# con-right-bot.net
KiCad netlist of a schematic drawn in Altium Designer
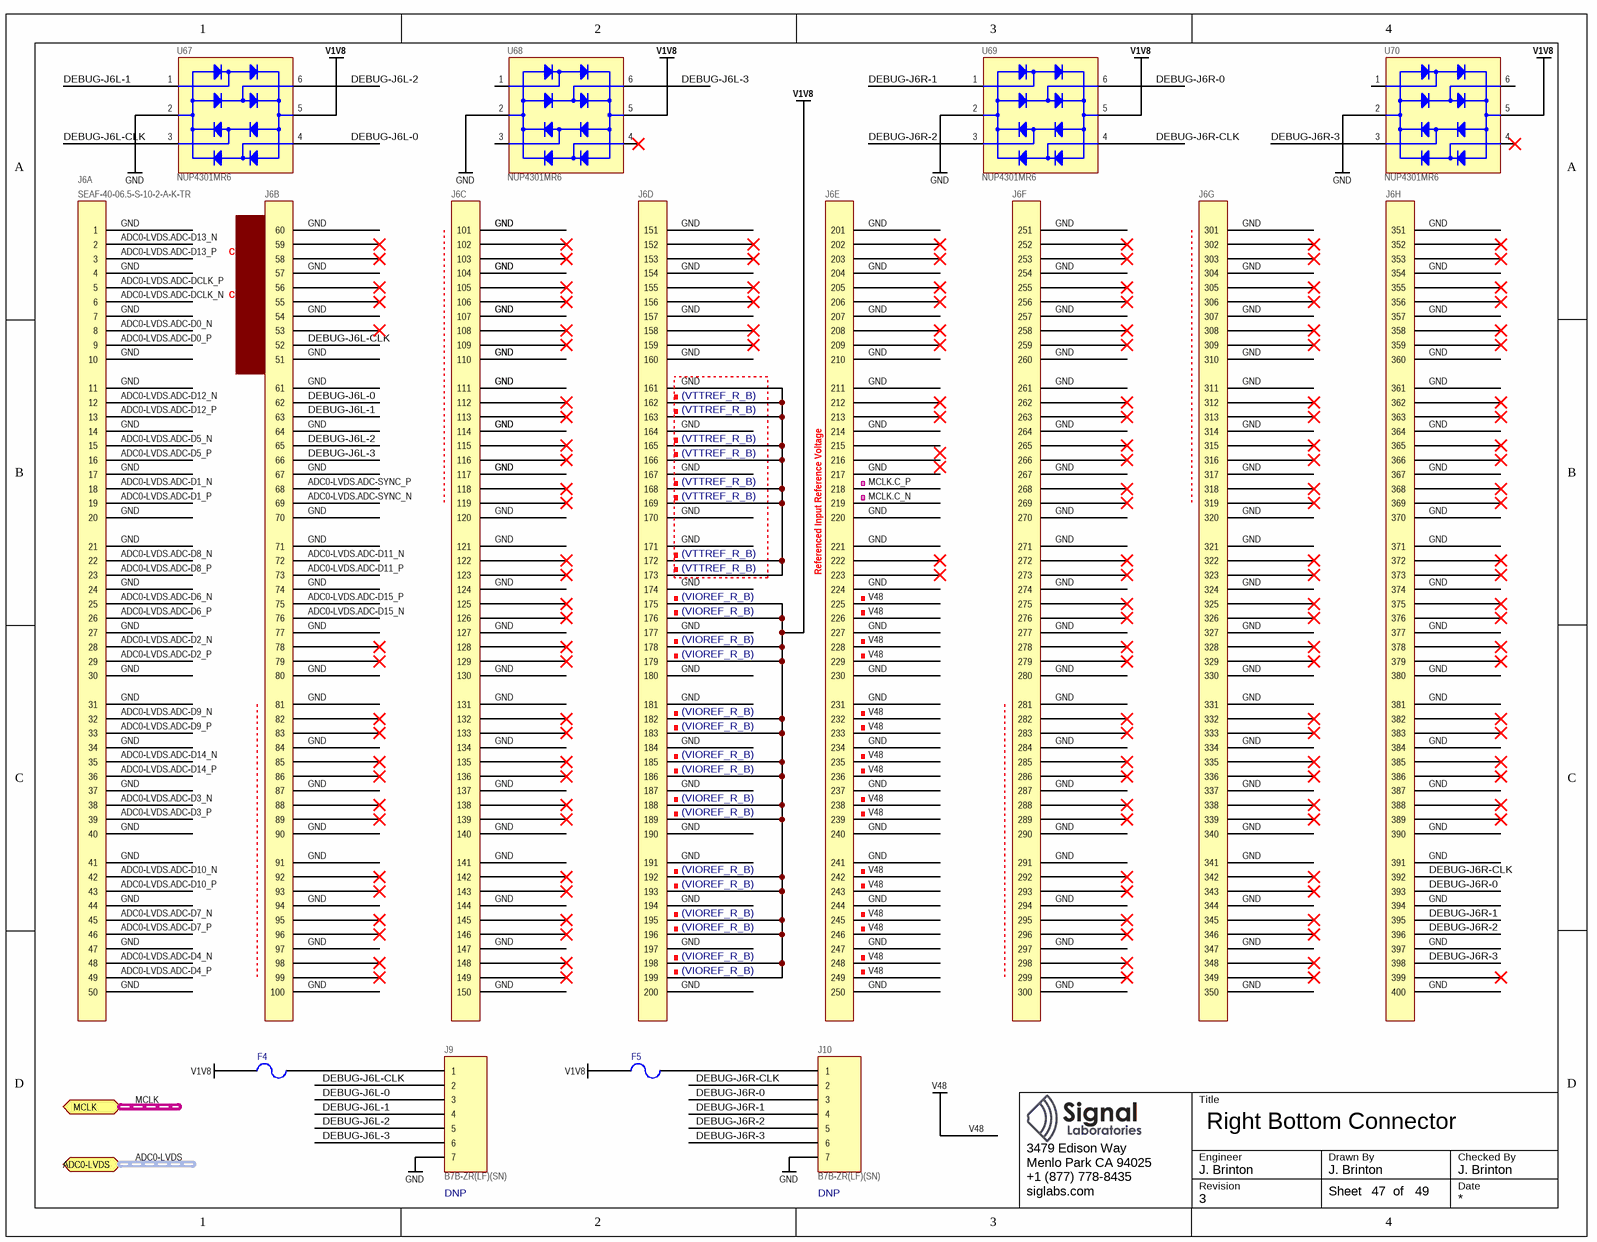
[diagram p0: con-right-bot.SchDoc]

(export (version "E")
  (design (tool "Eeschema 10.0.6"))
  (components
    (comp (ref "F4")
      (value "0ZCJ0020FF2E")
      (footprint "generic:1206")
      (description "PTC Resettable Fuse, 0.2A, 30V, SMD 1206")
      (fields (field (name "MANUFACTURER") "Bell Fuse"))
      (libsource (lib "bel-fuse") (part "0ZCJ0020FF2E"))
    )
    (comp (ref "F5")
      (value "0ZCJ0020FF2E")
      (footprint "generic:1206")
      (description "PTC Resettable Fuse, 0.2A, 30V, SMD 1206")
      (fields (field (name "MANUFACTURER") "Bell Fuse"))
      (libsource (lib "bel-fuse") (part "0ZCJ0020FF2E"))
    )
    (comp (ref "J6")
      (value "SEAF-40-06.5-S-10-2-A-K-TR")
      (footprint "samtec:SEAF-40-06.5-S-10-2-A-K-TR")
      (description "Terminal Array Assembly, Surface Mount, 0.050\" Pitch, 400 Pins")
      (fields (field (name "MANUFACTURER") "Samtec"))
      (libsource (lib "samtec") (part "SEAF-40-06.5-S-10-2-A-K-TR"))
    )
    (comp (ref "J9")
      (value "B7B-ZR(LF)(SN)")
      (footprint "jst:B7B-ZR")
      (description "Through-hole Shrouded Header 7-Position")
      (fields (field (name "MANUFACTURER") "JST") (field (name "DO NOT PLACE") "DNP"))
      (libsource (lib "jst") (part "B7B-ZR(LF)(SN)"))
    )
    (comp (ref "J10")
      (value "B7B-ZR(LF)(SN)")
      (footprint "jst:B7B-ZR")
      (description "Through-hole Shrouded Header 7-Position")
      (fields (field (name "MANUFACTURER") "JST") (field (name "DO NOT PLACE") "DNP"))
      (libsource (lib "jst") (part "B7B-ZR(LF)(SN)"))
    )
    (comp (ref "U67")
      (value "NUP4301MR6")
      (footprint "generic:SOT23-6")
      (description "4-Lane TVS Diode Array")
      (fields (field (name "MANUFACTURER") "On Semiconductor"))
      (libsource (lib "on_semi") (part "NUP4301MR6"))
    )
    (comp (ref "U68")
      (value "NUP4301MR6")
      (footprint "generic:SOT23-6")
      (description "4-Lane TVS Diode Array")
      (fields (field (name "MANUFACTURER") "On Semiconductor"))
      (libsource (lib "on_semi") (part "NUP4301MR6"))
    )
    (comp (ref "U69")
      (value "NUP4301MR6")
      (footprint "generic:SOT23-6")
      (description "4-Lane TVS Diode Array")
      (fields (field (name "MANUFACTURER") "On Semiconductor"))
      (libsource (lib "on_semi") (part "NUP4301MR6"))
    )
    (comp (ref "U70")
      (value "NUP4301MR6")
      (footprint "generic:SOT23-6")
      (description "4-Lane TVS Diode Array")
      (fields (field (name "MANUFACTURER") "On Semiconductor"))
      (libsource (lib "on_semi") (part "NUP4301MR6"))
    )
  )
  (nets
    (net (code "3") (name "/ADC0-LVDS.ADC-D0_N") (class "Default")
      (node (ref "J6") (pin "8") (pinfunction "8_8") (pintype "passive"))
    )
    (net (code "4") (name "/ADC0-LVDS.ADC-D0_P") (class "Default")
      (node (ref "J6") (pin "9") (pinfunction "9_9") (pintype "passive"))
    )
    (net (code "5") (name "/ADC0-LVDS.ADC-D1_N") (class "Default")
      (node (ref "J6") (pin "18") (pinfunction "18_18") (pintype "passive"))
    )
    (net (code "6") (name "/ADC0-LVDS.ADC-D1_P") (class "Default")
      (node (ref "J6") (pin "19") (pinfunction "19_19") (pintype "passive"))
    )
    (net (code "7") (name "/ADC0-LVDS.ADC-D2_N") (class "Default")
      (node (ref "J6") (pin "28") (pinfunction "28_28") (pintype "passive"))
    )
    (net (code "8") (name "/ADC0-LVDS.ADC-D2_P") (class "Default")
      (node (ref "J6") (pin "29") (pinfunction "29_29") (pintype "passive"))
    )
    (net (code "9") (name "/ADC0-LVDS.ADC-D3_N") (class "Default")
      (node (ref "J6") (pin "38") (pinfunction "38_38") (pintype "passive"))
    )
    (net (code "10") (name "/ADC0-LVDS.ADC-D3_P") (class "Default")
      (node (ref "J6") (pin "39") (pinfunction "39_39") (pintype "passive"))
    )
    (net (code "11") (name "/ADC0-LVDS.ADC-D4_N") (class "Default")
      (node (ref "J6") (pin "48") (pinfunction "48_48") (pintype "passive"))
    )
    (net (code "12") (name "/ADC0-LVDS.ADC-D4_P") (class "Default")
      (node (ref "J6") (pin "49") (pinfunction "49_49") (pintype "passive"))
    )
    (net (code "13") (name "/ADC0-LVDS.ADC-D5_N") (class "Default")
      (node (ref "J6") (pin "15") (pinfunction "15_15") (pintype "passive"))
    )
    (net (code "14") (name "/ADC0-LVDS.ADC-D5_P") (class "Default")
      (node (ref "J6") (pin "16") (pinfunction "16_16") (pintype "passive"))
    )
    (net (code "15") (name "/ADC0-LVDS.ADC-D6_N") (class "Default")
      (node (ref "J6") (pin "25") (pinfunction "25_25") (pintype "passive"))
    )
    (net (code "16") (name "/ADC0-LVDS.ADC-D6_P") (class "Default")
      (node (ref "J6") (pin "26") (pinfunction "26_26") (pintype "passive"))
    )
    (net (code "17") (name "/ADC0-LVDS.ADC-D7_N") (class "Default")
      (node (ref "J6") (pin "45") (pinfunction "45_45") (pintype "passive"))
    )
    (net (code "18") (name "/ADC0-LVDS.ADC-D7_P") (class "Default")
      (node (ref "J6") (pin "46") (pinfunction "46_46") (pintype "passive"))
    )
    (net (code "19") (name "/ADC0-LVDS.ADC-D8_N") (class "Default")
      (node (ref "J6") (pin "22") (pinfunction "22_22") (pintype "passive"))
    )
    (net (code "20") (name "/ADC0-LVDS.ADC-D8_P") (class "Default")
      (node (ref "J6") (pin "23") (pinfunction "23_23") (pintype "passive"))
    )
    (net (code "21") (name "/ADC0-LVDS.ADC-D9_N") (class "Default")
      (node (ref "J6") (pin "32") (pinfunction "32_32") (pintype "passive"))
    )
    (net (code "22") (name "/ADC0-LVDS.ADC-D9_P") (class "Default")
      (node (ref "J6") (pin "33") (pinfunction "33_33") (pintype "passive"))
    )
    (net (code "23") (name "/ADC0-LVDS.ADC-D10_N") (class "Default")
      (node (ref "J6") (pin "42") (pinfunction "42_42") (pintype "passive"))
    )
    (net (code "24") (name "/ADC0-LVDS.ADC-D10_P") (class "Default")
      (node (ref "J6") (pin "43") (pinfunction "43_43") (pintype "passive"))
    )
    (net (code "25") (name "/ADC0-LVDS.ADC-D11_N") (class "Default")
      (node (ref "J6") (pin "72") (pinfunction "72_72") (pintype "passive"))
    )
    (net (code "26") (name "/ADC0-LVDS.ADC-D11_P") (class "Default")
      (node (ref "J6") (pin "73") (pinfunction "73_73") (pintype "passive"))
    )
    (net (code "27") (name "/ADC0-LVDS.ADC-D12_N") (class "Default")
      (node (ref "J6") (pin "12") (pinfunction "12_12") (pintype "passive"))
    )
    (net (code "28") (name "/ADC0-LVDS.ADC-D12_P") (class "Default")
      (node (ref "J6") (pin "13") (pinfunction "13_13") (pintype "passive"))
    )
    (net (code "29") (name "/ADC0-LVDS.ADC-D13_N") (class "Default")
      (node (ref "J6") (pin "2") (pinfunction "2_2") (pintype "passive"))
    )
    (net (code "30") (name "/ADC0-LVDS.ADC-D13_P") (class "Default")
      (node (ref "J6") (pin "3") (pinfunction "3_3") (pintype "passive"))
    )
    (net (code "31") (name "/ADC0-LVDS.ADC-D14_N") (class "Default")
      (node (ref "J6") (pin "35") (pinfunction "35_35") (pintype "passive"))
    )
    (net (code "32") (name "/ADC0-LVDS.ADC-D14_P") (class "Default")
      (node (ref "J6") (pin "36") (pinfunction "36_36") (pintype "passive"))
    )
    (net (code "33") (name "/ADC0-LVDS.ADC-D15_N") (class "Default")
      (node (ref "J6") (pin "76") (pinfunction "76_76") (pintype "passive"))
    )
    (net (code "34") (name "/ADC0-LVDS.ADC-D15_P") (class "Default")
      (node (ref "J6") (pin "75") (pinfunction "75_75") (pintype "passive"))
    )
    (net (code "35") (name "/ADC0-LVDS.ADC-DCLK_N") (class "Default")
      (node (ref "J6") (pin "6") (pinfunction "6_6") (pintype "passive"))
    )
    (net (code "36") (name "/ADC0-LVDS.ADC-DCLK_P") (class "Default")
      (node (ref "J6") (pin "5") (pinfunction "5_5") (pintype "passive"))
    )
    (net (code "37") (name "/ADC0-LVDS.ADC-SYNC_N") (class "Default")
      (node (ref "J6") (pin "69") (pinfunction "69_69") (pintype "passive"))
    )
    (net (code "38") (name "/ADC0-LVDS.ADC-SYNC_P") (class "Default")
      (node (ref "J6") (pin "68") (pinfunction "68_68") (pintype "passive"))
    )
    (net (code "39") (name "/DEBUG-J6L-0") (class "Default")
      (node (ref "J6") (pin "62") (pinfunction "62_62") (pintype "passive"))
      (node (ref "J9") (pin "3") (pinfunction "3_3") (pintype "passive"))
      (node (ref "U67") (pin "4") (pinfunction "C_4") (pintype "passive"))
    )
    (net (code "40") (name "/DEBUG-J6L-1") (class "Default")
      (node (ref "J6") (pin "63") (pinfunction "63_63") (pintype "passive"))
      (node (ref "J9") (pin "4") (pinfunction "4_4") (pintype "passive"))
      (node (ref "U67") (pin "1") (pinfunction "A_1") (pintype "passive"))
    )
    (net (code "41") (name "/DEBUG-J6L-2") (class "Default")
      (node (ref "J6") (pin "65") (pinfunction "65_65") (pintype "passive"))
      (node (ref "J9") (pin "5") (pinfunction "5_5") (pintype "passive"))
      (node (ref "U67") (pin "6") (pinfunction "D_6") (pintype "passive"))
    )
    (net (code "42") (name "/DEBUG-J6L-3") (class "Default")
      (node (ref "J6") (pin "66") (pinfunction "66_66") (pintype "passive"))
      (node (ref "J9") (pin "6") (pinfunction "6_6") (pintype "passive"))
      (node (ref "U68") (pin "6") (pinfunction "D_6") (pintype "passive"))
    )
    (net (code "43") (name "/DEBUG-J6L-CLK") (class "Default")
      (node (ref "J6") (pin "52") (pinfunction "52_52") (pintype "passive"))
      (node (ref "J9") (pin "2") (pinfunction "2_2") (pintype "passive"))
      (node (ref "U67") (pin "3") (pinfunction "B_3") (pintype "passive"))
    )
    (net (code "44") (name "/DEBUG-J6R-0") (class "Default")
      (node (ref "J10") (pin "3") (pinfunction "3_3") (pintype "passive"))
      (node (ref "J6") (pin "393") (pinfunction "393_393") (pintype "passive"))
      (node (ref "U69") (pin "6") (pinfunction "D_6") (pintype "passive"))
    )
    (net (code "45") (name "/DEBUG-J6R-1") (class "Default")
      (node (ref "J10") (pin "4") (pinfunction "4_4") (pintype "passive"))
      (node (ref "J6") (pin "395") (pinfunction "395_395") (pintype "passive"))
      (node (ref "U69") (pin "1") (pinfunction "A_1") (pintype "passive"))
    )
    (net (code "46") (name "/DEBUG-J6R-2") (class "Default")
      (node (ref "J10") (pin "5") (pinfunction "5_5") (pintype "passive"))
      (node (ref "J6") (pin "396") (pinfunction "396_396") (pintype "passive"))
      (node (ref "U69") (pin "3") (pinfunction "B_3") (pintype "passive"))
    )
    (net (code "47") (name "/DEBUG-J6R-3") (class "Default")
      (node (ref "J10") (pin "6") (pinfunction "6_6") (pintype "passive"))
      (node (ref "J6") (pin "398") (pinfunction "398_398") (pintype "passive"))
      (node (ref "U70") (pin "3") (pinfunction "B_3") (pintype "passive"))
    )
    (net (code "48") (name "/DEBUG-J6R-CLK") (class "Default")
      (node (ref "J10") (pin "2") (pinfunction "2_2") (pintype "passive"))
      (node (ref "J6") (pin "392") (pinfunction "392_392") (pintype "passive"))
      (node (ref "U69") (pin "4") (pinfunction "C_4") (pintype "passive"))
    )
    (net (code "49") (name "/MCLK.C_N") (class "Default")
      (node (ref "J6") (pin "219") (pinfunction "219_219") (pintype "passive"))
    )
    (net (code "50") (name "/MCLK.C_P") (class "Default")
      (node (ref "J6") (pin "218") (pinfunction "218_218") (pintype "passive"))
    )
    (net (code "53") (name "GND") (class "Default")
      (node (ref "J10") (pin "7") (pinfunction "7_7") (pintype "passive"))
      (node (ref "J6") (pin "1") (pinfunction "1_1") (pintype "passive"))
      (node (ref "J6") (pin "10") (pinfunction "10_10") (pintype "passive"))
      (node (ref "J6") (pin "100") (pinfunction "100_100") (pintype "passive"))
      (node (ref "J6") (pin "101") (pinfunction "101_101") (pintype "passive"))
      (node (ref "J6") (pin "104") (pinfunction "104_104") (pintype "passive"))
      (node (ref "J6") (pin "107") (pinfunction "107_107") (pintype "passive"))
      (node (ref "J6") (pin "11") (pinfunction "11_11") (pintype "passive"))
      (node (ref "J6") (pin "110") (pinfunction "110_110") (pintype "passive"))
      (node (ref "J6") (pin "111") (pinfunction "111_111") (pintype "passive"))
      (node (ref "J6") (pin "114") (pinfunction "114_114") (pintype "passive"))
      (node (ref "J6") (pin "117") (pinfunction "117_117") (pintype "passive"))
      (node (ref "J6") (pin "120") (pinfunction "120_120") (pintype "passive"))
      (node (ref "J6") (pin "121") (pinfunction "121_121") (pintype "passive"))
      (node (ref "J6") (pin "124") (pinfunction "124_124") (pintype "passive"))
      (node (ref "J6") (pin "127") (pinfunction "127_127") (pintype "passive"))
      (node (ref "J6") (pin "130") (pinfunction "130_130") (pintype "passive"))
      (node (ref "J6") (pin "131") (pinfunction "131_131") (pintype "passive"))
      (node (ref "J6") (pin "134") (pinfunction "134_134") (pintype "passive"))
      (node (ref "J6") (pin "137") (pinfunction "137_137") (pintype "passive"))
      (node (ref "J6") (pin "14") (pinfunction "14_14") (pintype "passive"))
      (node (ref "J6") (pin "140") (pinfunction "140_140") (pintype "passive"))
      (node (ref "J6") (pin "141") (pinfunction "141_141") (pintype "passive"))
      (node (ref "J6") (pin "144") (pinfunction "144_144") (pintype "passive"))
      (node (ref "J6") (pin "147") (pinfunction "147_147") (pintype "passive"))
      (node (ref "J6") (pin "150") (pinfunction "150_150") (pintype "passive"))
      (node (ref "J6") (pin "151") (pinfunction "151_151") (pintype "passive"))
      (node (ref "J6") (pin "154") (pinfunction "154_154") (pintype "passive"))
      (node (ref "J6") (pin "157") (pinfunction "157_157") (pintype "passive"))
      (node (ref "J6") (pin "160") (pinfunction "160_160") (pintype "passive"))
      (node (ref "J6") (pin "161") (pinfunction "161_161") (pintype "passive"))
      (node (ref "J6") (pin "162") (pinfunction "162_162") (pintype "passive"))
      (node (ref "J6") (pin "163") (pinfunction "163_163") (pintype "passive"))
      (node (ref "J6") (pin "164") (pinfunction "164_164") (pintype "passive"))
      (node (ref "J6") (pin "165") (pinfunction "165_165") (pintype "passive"))
      (node (ref "J6") (pin "166") (pinfunction "166_166") (pintype "passive"))
      (node (ref "J6") (pin "167") (pinfunction "167_167") (pintype "passive"))
      (node (ref "J6") (pin "168") (pinfunction "168_168") (pintype "passive"))
      (node (ref "J6") (pin "169") (pinfunction "169_169") (pintype "passive"))
      (node (ref "J6") (pin "17") (pinfunction "17_17") (pintype "passive"))
      (node (ref "J6") (pin "170") (pinfunction "170_170") (pintype "passive"))
      (node (ref "J6") (pin "171") (pinfunction "171_171") (pintype "passive"))
      (node (ref "J6") (pin "172") (pinfunction "172_172") (pintype "passive"))
      (node (ref "J6") (pin "173") (pinfunction "173_173") (pintype "passive"))
      (node (ref "J6") (pin "174") (pinfunction "174_174") (pintype "passive"))
      (node (ref "J6") (pin "177") (pinfunction "177_177") (pintype "passive"))
      (node (ref "J6") (pin "180") (pinfunction "180_180") (pintype "passive"))
      (node (ref "J6") (pin "181") (pinfunction "181_181") (pintype "passive"))
      (node (ref "J6") (pin "184") (pinfunction "184_184") (pintype "passive"))
      (node (ref "J6") (pin "187") (pinfunction "187_187") (pintype "passive"))
      (node (ref "J6") (pin "190") (pinfunction "190_190") (pintype "passive"))
      (node (ref "J6") (pin "191") (pinfunction "191_191") (pintype "passive"))
      (node (ref "J6") (pin "194") (pinfunction "194_194") (pintype "passive"))
      (node (ref "J6") (pin "197") (pinfunction "197_197") (pintype "passive"))
      (node (ref "J6") (pin "20") (pinfunction "20_20") (pintype "passive"))
      (node (ref "J6") (pin "200") (pinfunction "200_200") (pintype "passive"))
      (node (ref "J6") (pin "201") (pinfunction "201_201") (pintype "passive"))
      (node (ref "J6") (pin "204") (pinfunction "204_204") (pintype "passive"))
      (node (ref "J6") (pin "207") (pinfunction "207_207") (pintype "passive"))
      (node (ref "J6") (pin "21") (pinfunction "21_21") (pintype "passive"))
      (node (ref "J6") (pin "210") (pinfunction "210_210") (pintype "passive"))
      (node (ref "J6") (pin "211") (pinfunction "211_211") (pintype "passive"))
      (node (ref "J6") (pin "214") (pinfunction "214_214") (pintype "passive"))
      (node (ref "J6") (pin "217") (pinfunction "217_217") (pintype "passive"))
      (node (ref "J6") (pin "220") (pinfunction "220_220") (pintype "passive"))
      (node (ref "J6") (pin "221") (pinfunction "221_221") (pintype "passive"))
      (node (ref "J6") (pin "224") (pinfunction "224_224") (pintype "passive"))
      (node (ref "J6") (pin "227") (pinfunction "227_227") (pintype "passive"))
      (node (ref "J6") (pin "230") (pinfunction "230_230") (pintype "passive"))
      (node (ref "J6") (pin "231") (pinfunction "231_231") (pintype "passive"))
      (node (ref "J6") (pin "234") (pinfunction "234_234") (pintype "passive"))
      (node (ref "J6") (pin "237") (pinfunction "237_237") (pintype "passive"))
      (node (ref "J6") (pin "24") (pinfunction "24_24") (pintype "passive"))
      (node (ref "J6") (pin "240") (pinfunction "240_240") (pintype "passive"))
      (node (ref "J6") (pin "241") (pinfunction "241_241") (pintype "passive"))
      (node (ref "J6") (pin "244") (pinfunction "244_244") (pintype "passive"))
      (node (ref "J6") (pin "247") (pinfunction "247_247") (pintype "passive"))
      (node (ref "J6") (pin "250") (pinfunction "250_250") (pintype "passive"))
      (node (ref "J6") (pin "251") (pinfunction "251_251") (pintype "passive"))
      (node (ref "J6") (pin "254") (pinfunction "254_254") (pintype "passive"))
      (node (ref "J6") (pin "257") (pinfunction "257_257") (pintype "passive"))
      (node (ref "J6") (pin "260") (pinfunction "260_260") (pintype "passive"))
      (node (ref "J6") (pin "261") (pinfunction "261_261") (pintype "passive"))
      (node (ref "J6") (pin "264") (pinfunction "264_264") (pintype "passive"))
      (node (ref "J6") (pin "267") (pinfunction "267_267") (pintype "passive"))
      (node (ref "J6") (pin "27") (pinfunction "27_27") (pintype "passive"))
      (node (ref "J6") (pin "270") (pinfunction "270_270") (pintype "passive"))
      (node (ref "J6") (pin "271") (pinfunction "271_271") (pintype "passive"))
      (node (ref "J6") (pin "274") (pinfunction "274_274") (pintype "passive"))
      (node (ref "J6") (pin "277") (pinfunction "277_277") (pintype "passive"))
      (node (ref "J6") (pin "280") (pinfunction "280_280") (pintype "passive"))
      (node (ref "J6") (pin "281") (pinfunction "281_281") (pintype "passive"))
      (node (ref "J6") (pin "284") (pinfunction "284_284") (pintype "passive"))
      (node (ref "J6") (pin "287") (pinfunction "287_287") (pintype "passive"))
      (node (ref "J6") (pin "290") (pinfunction "290_290") (pintype "passive"))
      (node (ref "J6") (pin "291") (pinfunction "291_291") (pintype "passive"))
      (node (ref "J6") (pin "294") (pinfunction "294_294") (pintype "passive"))
      (node (ref "J6") (pin "297") (pinfunction "297_297") (pintype "passive"))
      (node (ref "J6") (pin "30") (pinfunction "30_30") (pintype "passive"))
      (node (ref "J6") (pin "300") (pinfunction "300_300") (pintype "passive"))
      (node (ref "J6") (pin "301") (pinfunction "301_301") (pintype "passive"))
      (node (ref "J6") (pin "304") (pinfunction "304_304") (pintype "passive"))
      (node (ref "J6") (pin "307") (pinfunction "307_307") (pintype "passive"))
      (node (ref "J6") (pin "31") (pinfunction "31_31") (pintype "passive"))
      (node (ref "J6") (pin "310") (pinfunction "310_310") (pintype "passive"))
      (node (ref "J6") (pin "311") (pinfunction "311_311") (pintype "passive"))
      (node (ref "J6") (pin "314") (pinfunction "314_314") (pintype "passive"))
      (node (ref "J6") (pin "317") (pinfunction "317_317") (pintype "passive"))
      (node (ref "J6") (pin "320") (pinfunction "320_320") (pintype "passive"))
      (node (ref "J6") (pin "321") (pinfunction "321_321") (pintype "passive"))
      (node (ref "J6") (pin "324") (pinfunction "324_324") (pintype "passive"))
      (node (ref "J6") (pin "327") (pinfunction "327_327") (pintype "passive"))
      (node (ref "J6") (pin "330") (pinfunction "330_330") (pintype "passive"))
      (node (ref "J6") (pin "331") (pinfunction "331_331") (pintype "passive"))
      (node (ref "J6") (pin "334") (pinfunction "334_334") (pintype "passive"))
      (node (ref "J6") (pin "337") (pinfunction "337_337") (pintype "passive"))
      (node (ref "J6") (pin "34") (pinfunction "34_34") (pintype "passive"))
      (node (ref "J6") (pin "340") (pinfunction "340_340") (pintype "passive"))
      (node (ref "J6") (pin "341") (pinfunction "341_341") (pintype "passive"))
      (node (ref "J6") (pin "344") (pinfunction "344_344") (pintype "passive"))
      (node (ref "J6") (pin "347") (pinfunction "347_347") (pintype "passive"))
      (node (ref "J6") (pin "350") (pinfunction "350_350") (pintype "passive"))
      (node (ref "J6") (pin "351") (pinfunction "351_351") (pintype "passive"))
      (node (ref "J6") (pin "354") (pinfunction "354_354") (pintype "passive"))
      (node (ref "J6") (pin "357") (pinfunction "357_357") (pintype "passive"))
      (node (ref "J6") (pin "360") (pinfunction "360_360") (pintype "passive"))
      (node (ref "J6") (pin "361") (pinfunction "361_361") (pintype "passive"))
      (node (ref "J6") (pin "364") (pinfunction "364_364") (pintype "passive"))
      (node (ref "J6") (pin "367") (pinfunction "367_367") (pintype "passive"))
      (node (ref "J6") (pin "37") (pinfunction "37_37") (pintype "passive"))
      (node (ref "J6") (pin "370") (pinfunction "370_370") (pintype "passive"))
      (node (ref "J6") (pin "371") (pinfunction "371_371") (pintype "passive"))
      (node (ref "J6") (pin "374") (pinfunction "374_374") (pintype "passive"))
      (node (ref "J6") (pin "377") (pinfunction "377_377") (pintype "passive"))
      (node (ref "J6") (pin "380") (pinfunction "380_380") (pintype "passive"))
      (node (ref "J6") (pin "381") (pinfunction "381_381") (pintype "passive"))
      (node (ref "J6") (pin "384") (pinfunction "384_384") (pintype "passive"))
      (node (ref "J6") (pin "387") (pinfunction "387_387") (pintype "passive"))
      (node (ref "J6") (pin "390") (pinfunction "390_390") (pintype "passive"))
      (node (ref "J6") (pin "391") (pinfunction "391_391") (pintype "passive"))
      (node (ref "J6") (pin "394") (pinfunction "394_394") (pintype "passive"))
      (node (ref "J6") (pin "397") (pinfunction "397_397") (pintype "passive"))
      (node (ref "J6") (pin "4") (pinfunction "4_4") (pintype "passive"))
      (node (ref "J6") (pin "40") (pinfunction "40_40") (pintype "passive"))
      (node (ref "J6") (pin "400") (pinfunction "400_400") (pintype "passive"))
      (node (ref "J6") (pin "41") (pinfunction "41_41") (pintype "passive"))
      (node (ref "J6") (pin "44") (pinfunction "44_44") (pintype "passive"))
      (node (ref "J6") (pin "47") (pinfunction "47_47") (pintype "passive"))
      (node (ref "J6") (pin "50") (pinfunction "50_50") (pintype "passive"))
      (node (ref "J6") (pin "51") (pinfunction "51_51") (pintype "passive"))
      (node (ref "J6") (pin "54") (pinfunction "54_54") (pintype "passive"))
      (node (ref "J6") (pin "57") (pinfunction "57_57") (pintype "passive"))
      (node (ref "J6") (pin "60") (pinfunction "60_60") (pintype "passive"))
      (node (ref "J6") (pin "61") (pinfunction "61_61") (pintype "passive"))
      (node (ref "J6") (pin "64") (pinfunction "64_64") (pintype "passive"))
      (node (ref "J6") (pin "67") (pinfunction "67_67") (pintype "passive"))
      (node (ref "J6") (pin "7") (pinfunction "7_7") (pintype "passive"))
      (node (ref "J6") (pin "70") (pinfunction "70_70") (pintype "passive"))
      (node (ref "J6") (pin "71") (pinfunction "71_71") (pintype "passive"))
      (node (ref "J6") (pin "74") (pinfunction "74_74") (pintype "passive"))
      (node (ref "J6") (pin "77") (pinfunction "77_77") (pintype "passive"))
      (node (ref "J6") (pin "80") (pinfunction "80_80") (pintype "passive"))
      (node (ref "J6") (pin "81") (pinfunction "81_81") (pintype "passive"))
      (node (ref "J6") (pin "84") (pinfunction "84_84") (pintype "passive"))
      (node (ref "J6") (pin "87") (pinfunction "87_87") (pintype "passive"))
      (node (ref "J6") (pin "90") (pinfunction "90_90") (pintype "passive"))
      (node (ref "J6") (pin "91") (pinfunction "91_91") (pintype "passive"))
      (node (ref "J6") (pin "94") (pinfunction "94_94") (pintype "passive"))
      (node (ref "J6") (pin "97") (pinfunction "97_97") (pintype "passive"))
      (node (ref "J9") (pin "7") (pinfunction "7_7") (pintype "passive"))
      (node (ref "U67") (pin "2") (pinfunction "VN_2") (pintype "passive"))
      (node (ref "U68") (pin "2") (pinfunction "VN_2") (pintype "passive"))
      (node (ref "U69") (pin "2") (pinfunction "VN_2") (pintype "passive"))
      (node (ref "U70") (pin "2") (pinfunction "VN_2") (pintype "passive"))
    )
    (net (code "54") (name "Net-(F4-Pad1)") (class "Default")
      (node (ref "F4") (pin "1") (pinfunction "1_1") (pintype "passive"))
      (node (ref "J9") (pin "1") (pinfunction "1_1") (pintype "passive"))
    )
    (net (code "55") (name "Net-(F5-Pad1)") (class "Default")
      (node (ref "F5") (pin "1") (pinfunction "1_1") (pintype "passive"))
      (node (ref "J10") (pin "1") (pinfunction "1_1") (pintype "passive"))
    )
    (net (code "56") (name "V1V8") (class "Default")
      (node (ref "F4") (pin "2") (pinfunction "2_2") (pintype "passive"))
      (node (ref "F5") (pin "2") (pinfunction "2_2") (pintype "passive"))
      (node (ref "J6") (pin "175") (pinfunction "175_175") (pintype "passive"))
      (node (ref "J6") (pin "176") (pinfunction "176_176") (pintype "passive"))
      (node (ref "J6") (pin "178") (pinfunction "178_178") (pintype "passive"))
      (node (ref "J6") (pin "179") (pinfunction "179_179") (pintype "passive"))
      (node (ref "J6") (pin "182") (pinfunction "182_182") (pintype "passive"))
      (node (ref "J6") (pin "183") (pinfunction "183_183") (pintype "passive"))
      (node (ref "J6") (pin "185") (pinfunction "185_185") (pintype "passive"))
      (node (ref "J6") (pin "186") (pinfunction "186_186") (pintype "passive"))
      (node (ref "J6") (pin "188") (pinfunction "188_188") (pintype "passive"))
      (node (ref "J6") (pin "189") (pinfunction "189_189") (pintype "passive"))
      (node (ref "J6") (pin "192") (pinfunction "192_192") (pintype "passive"))
      (node (ref "J6") (pin "193") (pinfunction "193_193") (pintype "passive"))
      (node (ref "J6") (pin "195") (pinfunction "195_195") (pintype "passive"))
      (node (ref "J6") (pin "196") (pinfunction "196_196") (pintype "passive"))
      (node (ref "J6") (pin "198") (pinfunction "198_198") (pintype "passive"))
      (node (ref "J6") (pin "199") (pinfunction "199_199") (pintype "passive"))
      (node (ref "U67") (pin "5") (pinfunction "VP_5") (pintype "passive"))
      (node (ref "U68") (pin "5") (pinfunction "VP_5") (pintype "passive"))
      (node (ref "U69") (pin "5") (pinfunction "VP_5") (pintype "passive"))
      (node (ref "U70") (pin "5") (pinfunction "VP_5") (pintype "passive"))
    )
    (net (code "57") (name "V48") (class "Default")
      (node (ref "J6") (pin "225") (pinfunction "225_225") (pintype "passive"))
      (node (ref "J6") (pin "226") (pinfunction "226_226") (pintype "passive"))
      (node (ref "J6") (pin "228") (pinfunction "228_228") (pintype "passive"))
      (node (ref "J6") (pin "229") (pinfunction "229_229") (pintype "passive"))
      (node (ref "J6") (pin "232") (pinfunction "232_232") (pintype "passive"))
      (node (ref "J6") (pin "233") (pinfunction "233_233") (pintype "passive"))
      (node (ref "J6") (pin "235") (pinfunction "235_235") (pintype "passive"))
      (node (ref "J6") (pin "236") (pinfunction "236_236") (pintype "passive"))
      (node (ref "J6") (pin "238") (pinfunction "238_238") (pintype "passive"))
      (node (ref "J6") (pin "239") (pinfunction "239_239") (pintype "passive"))
      (node (ref "J6") (pin "242") (pinfunction "242_242") (pintype "passive"))
      (node (ref "J6") (pin "243") (pinfunction "243_243") (pintype "passive"))
      (node (ref "J6") (pin "245") (pinfunction "245_245") (pintype "passive"))
      (node (ref "J6") (pin "246") (pinfunction "246_246") (pintype "passive"))
      (node (ref "J6") (pin "248") (pinfunction "248_248") (pintype "passive"))
      (node (ref "J6") (pin "249") (pinfunction "249_249") (pintype "passive"))
    )
    (net (code "58") (name "unconnected-(J6-Pad53)") (class "Default")
      (node (ref "J6") (pin "53") (pinfunction "53_53") (pintype "passive+no_connect"))
    )
    (net (code "59") (name "unconnected-(J6-Pad55)") (class "Default")
      (node (ref "J6") (pin "55") (pinfunction "55_55") (pintype "passive+no_connect"))
    )
    (net (code "60") (name "unconnected-(J6-Pad56)") (class "Default")
      (node (ref "J6") (pin "56") (pinfunction "56_56") (pintype "passive+no_connect"))
    )
    (net (code "61") (name "unconnected-(J6-Pad58)") (class "Default")
      (node (ref "J6") (pin "58") (pinfunction "58_58") (pintype "passive+no_connect"))
    )
    (net (code "62") (name "unconnected-(J6-Pad59)") (class "Default")
      (node (ref "J6") (pin "59") (pinfunction "59_59") (pintype "passive+no_connect"))
    )
    (net (code "63") (name "unconnected-(J6-Pad78)") (class "Default")
      (node (ref "J6") (pin "78") (pinfunction "78_78") (pintype "passive+no_connect"))
    )
    (net (code "64") (name "unconnected-(J6-Pad79)") (class "Default")
      (node (ref "J6") (pin "79") (pinfunction "79_79") (pintype "passive+no_connect"))
    )
    (net (code "65") (name "unconnected-(J6-Pad82)") (class "Default")
      (node (ref "J6") (pin "82") (pinfunction "82_82") (pintype "passive+no_connect"))
    )
    (net (code "66") (name "unconnected-(J6-Pad83)") (class "Default")
      (node (ref "J6") (pin "83") (pinfunction "83_83") (pintype "passive+no_connect"))
    )
    (net (code "67") (name "unconnected-(J6-Pad85)") (class "Default")
      (node (ref "J6") (pin "85") (pinfunction "85_85") (pintype "passive+no_connect"))
    )
    (net (code "68") (name "unconnected-(J6-Pad86)") (class "Default")
      (node (ref "J6") (pin "86") (pinfunction "86_86") (pintype "passive+no_connect"))
    )
    (net (code "69") (name "unconnected-(J6-Pad88)") (class "Default")
      (node (ref "J6") (pin "88") (pinfunction "88_88") (pintype "passive+no_connect"))
    )
    (net (code "70") (name "unconnected-(J6-Pad89)") (class "Default")
      (node (ref "J6") (pin "89") (pinfunction "89_89") (pintype "passive+no_connect"))
    )
    (net (code "71") (name "unconnected-(J6-Pad92)") (class "Default")
      (node (ref "J6") (pin "92") (pinfunction "92_92") (pintype "passive+no_connect"))
    )
    (net (code "72") (name "unconnected-(J6-Pad93)") (class "Default")
      (node (ref "J6") (pin "93") (pinfunction "93_93") (pintype "passive+no_connect"))
    )
    (net (code "73") (name "unconnected-(J6-Pad95)") (class "Default")
      (node (ref "J6") (pin "95") (pinfunction "95_95") (pintype "passive+no_connect"))
    )
    (net (code "74") (name "unconnected-(J6-Pad96)") (class "Default")
      (node (ref "J6") (pin "96") (pinfunction "96_96") (pintype "passive+no_connect"))
    )
    (net (code "75") (name "unconnected-(J6-Pad98)") (class "Default")
      (node (ref "J6") (pin "98") (pinfunction "98_98") (pintype "passive+no_connect"))
    )
    (net (code "76") (name "unconnected-(J6-Pad99)") (class "Default")
      (node (ref "J6") (pin "99") (pinfunction "99_99") (pintype "passive+no_connect"))
    )
    (net (code "77") (name "unconnected-(J6-Pad102)") (class "Default")
      (node (ref "J6") (pin "102") (pinfunction "102_102") (pintype "passive+no_connect"))
    )
    (net (code "78") (name "unconnected-(J6-Pad103)") (class "Default")
      (node (ref "J6") (pin "103") (pinfunction "103_103") (pintype "passive+no_connect"))
    )
    (net (code "79") (name "unconnected-(J6-Pad105)") (class "Default")
      (node (ref "J6") (pin "105") (pinfunction "105_105") (pintype "passive+no_connect"))
    )
    (net (code "80") (name "unconnected-(J6-Pad106)") (class "Default")
      (node (ref "J6") (pin "106") (pinfunction "106_106") (pintype "passive+no_connect"))
    )
    (net (code "81") (name "unconnected-(J6-Pad108)") (class "Default")
      (node (ref "J6") (pin "108") (pinfunction "108_108") (pintype "passive+no_connect"))
    )
    (net (code "82") (name "unconnected-(J6-Pad109)") (class "Default")
      (node (ref "J6") (pin "109") (pinfunction "109_109") (pintype "passive+no_connect"))
    )
    (net (code "83") (name "unconnected-(J6-Pad112)") (class "Default")
      (node (ref "J6") (pin "112") (pinfunction "112_112") (pintype "passive+no_connect"))
    )
    (net (code "84") (name "unconnected-(J6-Pad113)") (class "Default")
      (node (ref "J6") (pin "113") (pinfunction "113_113") (pintype "passive+no_connect"))
    )
    (net (code "85") (name "unconnected-(J6-Pad115)") (class "Default")
      (node (ref "J6") (pin "115") (pinfunction "115_115") (pintype "passive+no_connect"))
    )
    (net (code "86") (name "unconnected-(J6-Pad116)") (class "Default")
      (node (ref "J6") (pin "116") (pinfunction "116_116") (pintype "passive+no_connect"))
    )
    (net (code "87") (name "unconnected-(J6-Pad118)") (class "Default")
      (node (ref "J6") (pin "118") (pinfunction "118_118") (pintype "passive+no_connect"))
    )
    (net (code "88") (name "unconnected-(J6-Pad119)") (class "Default")
      (node (ref "J6") (pin "119") (pinfunction "119_119") (pintype "passive+no_connect"))
    )
    (net (code "89") (name "unconnected-(J6-Pad122)") (class "Default")
      (node (ref "J6") (pin "122") (pinfunction "122_122") (pintype "passive+no_connect"))
    )
    (net (code "90") (name "unconnected-(J6-Pad123)") (class "Default")
      (node (ref "J6") (pin "123") (pinfunction "123_123") (pintype "passive+no_connect"))
    )
    (net (code "91") (name "unconnected-(J6-Pad125)") (class "Default")
      (node (ref "J6") (pin "125") (pinfunction "125_125") (pintype "passive+no_connect"))
    )
    (net (code "92") (name "unconnected-(J6-Pad126)") (class "Default")
      (node (ref "J6") (pin "126") (pinfunction "126_126") (pintype "passive+no_connect"))
    )
    (net (code "93") (name "unconnected-(J6-Pad128)") (class "Default")
      (node (ref "J6") (pin "128") (pinfunction "128_128") (pintype "passive+no_connect"))
    )
    (net (code "94") (name "unconnected-(J6-Pad129)") (class "Default")
      (node (ref "J6") (pin "129") (pinfunction "129_129") (pintype "passive+no_connect"))
    )
    (net (code "95") (name "unconnected-(J6-Pad132)") (class "Default")
      (node (ref "J6") (pin "132") (pinfunction "132_132") (pintype "passive+no_connect"))
    )
    (net (code "96") (name "unconnected-(J6-Pad133)") (class "Default")
      (node (ref "J6") (pin "133") (pinfunction "133_133") (pintype "passive+no_connect"))
    )
    (net (code "97") (name "unconnected-(J6-Pad135)") (class "Default")
      (node (ref "J6") (pin "135") (pinfunction "135_135") (pintype "passive+no_connect"))
    )
    (net (code "98") (name "unconnected-(J6-Pad136)") (class "Default")
      (node (ref "J6") (pin "136") (pinfunction "136_136") (pintype "passive+no_connect"))
    )
    (net (code "99") (name "unconnected-(J6-Pad138)") (class "Default")
      (node (ref "J6") (pin "138") (pinfunction "138_138") (pintype "passive+no_connect"))
    )
    (net (code "100") (name "unconnected-(J6-Pad139)") (class "Default")
      (node (ref "J6") (pin "139") (pinfunction "139_139") (pintype "passive+no_connect"))
    )
    (net (code "101") (name "unconnected-(J6-Pad142)") (class "Default")
      (node (ref "J6") (pin "142") (pinfunction "142_142") (pintype "passive+no_connect"))
    )
    (net (code "102") (name "unconnected-(J6-Pad143)") (class "Default")
      (node (ref "J6") (pin "143") (pinfunction "143_143") (pintype "passive+no_connect"))
    )
    (net (code "103") (name "unconnected-(J6-Pad145)") (class "Default")
      (node (ref "J6") (pin "145") (pinfunction "145_145") (pintype "passive+no_connect"))
    )
    (net (code "104") (name "unconnected-(J6-Pad146)") (class "Default")
      (node (ref "J6") (pin "146") (pinfunction "146_146") (pintype "passive+no_connect"))
    )
    (net (code "105") (name "unconnected-(J6-Pad148)") (class "Default")
      (node (ref "J6") (pin "148") (pinfunction "148_148") (pintype "passive+no_connect"))
    )
    (net (code "106") (name "unconnected-(J6-Pad149)") (class "Default")
      (node (ref "J6") (pin "149") (pinfunction "149_149") (pintype "passive+no_connect"))
    )
    (net (code "107") (name "unconnected-(J6-Pad152)") (class "Default")
      (node (ref "J6") (pin "152") (pinfunction "152_152") (pintype "passive+no_connect"))
    )
    (net (code "108") (name "unconnected-(J6-Pad153)") (class "Default")
      (node (ref "J6") (pin "153") (pinfunction "153_153") (pintype "passive+no_connect"))
    )
    (net (code "109") (name "unconnected-(J6-Pad155)") (class "Default")
      (node (ref "J6") (pin "155") (pinfunction "155_155") (pintype "passive+no_connect"))
    )
    (net (code "110") (name "unconnected-(J6-Pad156)") (class "Default")
      (node (ref "J6") (pin "156") (pinfunction "156_156") (pintype "passive+no_connect"))
    )
    (net (code "111") (name "unconnected-(J6-Pad158)") (class "Default")
      (node (ref "J6") (pin "158") (pinfunction "158_158") (pintype "passive+no_connect"))
    )
    (net (code "112") (name "unconnected-(J6-Pad159)") (class "Default")
      (node (ref "J6") (pin "159") (pinfunction "159_159") (pintype "passive+no_connect"))
    )
    (net (code "113") (name "unconnected-(J6-Pad202)") (class "Default")
      (node (ref "J6") (pin "202") (pinfunction "202_202") (pintype "passive+no_connect"))
    )
    (net (code "114") (name "unconnected-(J6-Pad203)") (class "Default")
      (node (ref "J6") (pin "203") (pinfunction "203_203") (pintype "passive+no_connect"))
    )
    (net (code "115") (name "unconnected-(J6-Pad205)") (class "Default")
      (node (ref "J6") (pin "205") (pinfunction "205_205") (pintype "passive+no_connect"))
    )
    (net (code "116") (name "unconnected-(J6-Pad206)") (class "Default")
      (node (ref "J6") (pin "206") (pinfunction "206_206") (pintype "passive+no_connect"))
    )
    (net (code "117") (name "unconnected-(J6-Pad208)") (class "Default")
      (node (ref "J6") (pin "208") (pinfunction "208_208") (pintype "passive+no_connect"))
    )
    (net (code "118") (name "unconnected-(J6-Pad209)") (class "Default")
      (node (ref "J6") (pin "209") (pinfunction "209_209") (pintype "passive+no_connect"))
    )
    (net (code "119") (name "unconnected-(J6-Pad212)") (class "Default")
      (node (ref "J6") (pin "212") (pinfunction "212_212") (pintype "passive+no_connect"))
    )
    (net (code "120") (name "unconnected-(J6-Pad213)") (class "Default")
      (node (ref "J6") (pin "213") (pinfunction "213_213") (pintype "passive+no_connect"))
    )
    (net (code "121") (name "unconnected-(J6-Pad215)") (class "Default")
      (node (ref "J6") (pin "215") (pinfunction "215_215") (pintype "passive"))
    )
    (net (code "122") (name "unconnected-(J6-Pad216)") (class "Default")
      (node (ref "J6") (pin "216") (pinfunction "216_216") (pintype "passive"))
    )
    (net (code "123") (name "unconnected-(J6-Pad222)") (class "Default")
      (node (ref "J6") (pin "222") (pinfunction "222_222") (pintype "passive+no_connect"))
    )
    (net (code "124") (name "unconnected-(J6-Pad223)") (class "Default")
      (node (ref "J6") (pin "223") (pinfunction "223_223") (pintype "passive+no_connect"))
    )
    (net (code "125") (name "unconnected-(J6-Pad252)") (class "Default")
      (node (ref "J6") (pin "252") (pinfunction "252_252") (pintype "passive+no_connect"))
    )
    (net (code "126") (name "unconnected-(J6-Pad253)") (class "Default")
      (node (ref "J6") (pin "253") (pinfunction "253_253") (pintype "passive+no_connect"))
    )
    (net (code "127") (name "unconnected-(J6-Pad255)") (class "Default")
      (node (ref "J6") (pin "255") (pinfunction "255_255") (pintype "passive+no_connect"))
    )
    (net (code "128") (name "unconnected-(J6-Pad256)") (class "Default")
      (node (ref "J6") (pin "256") (pinfunction "256_256") (pintype "passive+no_connect"))
    )
    (net (code "129") (name "unconnected-(J6-Pad258)") (class "Default")
      (node (ref "J6") (pin "258") (pinfunction "258_258") (pintype "passive+no_connect"))
    )
    (net (code "130") (name "unconnected-(J6-Pad259)") (class "Default")
      (node (ref "J6") (pin "259") (pinfunction "259_259") (pintype "passive+no_connect"))
    )
    (net (code "131") (name "unconnected-(J6-Pad262)") (class "Default")
      (node (ref "J6") (pin "262") (pinfunction "262_262") (pintype "passive+no_connect"))
    )
    (net (code "132") (name "unconnected-(J6-Pad263)") (class "Default")
      (node (ref "J6") (pin "263") (pinfunction "263_263") (pintype "passive+no_connect"))
    )
    (net (code "133") (name "unconnected-(J6-Pad265)") (class "Default")
      (node (ref "J6") (pin "265") (pinfunction "265_265") (pintype "passive+no_connect"))
    )
    (net (code "134") (name "unconnected-(J6-Pad266)") (class "Default")
      (node (ref "J6") (pin "266") (pinfunction "266_266") (pintype "passive+no_connect"))
    )
    (net (code "135") (name "unconnected-(J6-Pad268)") (class "Default")
      (node (ref "J6") (pin "268") (pinfunction "268_268") (pintype "passive+no_connect"))
    )
    (net (code "136") (name "unconnected-(J6-Pad269)") (class "Default")
      (node (ref "J6") (pin "269") (pinfunction "269_269") (pintype "passive+no_connect"))
    )
    (net (code "137") (name "unconnected-(J6-Pad272)") (class "Default")
      (node (ref "J6") (pin "272") (pinfunction "272_272") (pintype "passive+no_connect"))
    )
    (net (code "138") (name "unconnected-(J6-Pad273)") (class "Default")
      (node (ref "J6") (pin "273") (pinfunction "273_273") (pintype "passive+no_connect"))
    )
    (net (code "139") (name "unconnected-(J6-Pad275)") (class "Default")
      (node (ref "J6") (pin "275") (pinfunction "275_275") (pintype "passive+no_connect"))
    )
    (net (code "140") (name "unconnected-(J6-Pad276)") (class "Default")
      (node (ref "J6") (pin "276") (pinfunction "276_276") (pintype "passive+no_connect"))
    )
    (net (code "141") (name "unconnected-(J6-Pad278)") (class "Default")
      (node (ref "J6") (pin "278") (pinfunction "278_278") (pintype "passive+no_connect"))
    )
    (net (code "142") (name "unconnected-(J6-Pad279)") (class "Default")
      (node (ref "J6") (pin "279") (pinfunction "279_279") (pintype "passive+no_connect"))
    )
    (net (code "143") (name "unconnected-(J6-Pad282)") (class "Default")
      (node (ref "J6") (pin "282") (pinfunction "282_282") (pintype "passive+no_connect"))
    )
    (net (code "144") (name "unconnected-(J6-Pad283)") (class "Default")
      (node (ref "J6") (pin "283") (pinfunction "283_283") (pintype "passive+no_connect"))
    )
    (net (code "145") (name "unconnected-(J6-Pad285)") (class "Default")
      (node (ref "J6") (pin "285") (pinfunction "285_285") (pintype "passive+no_connect"))
    )
    (net (code "146") (name "unconnected-(J6-Pad286)") (class "Default")
      (node (ref "J6") (pin "286") (pinfunction "286_286") (pintype "passive+no_connect"))
    )
    (net (code "147") (name "unconnected-(J6-Pad288)") (class "Default")
      (node (ref "J6") (pin "288") (pinfunction "288_288") (pintype "passive+no_connect"))
    )
    (net (code "148") (name "unconnected-(J6-Pad289)") (class "Default")
      (node (ref "J6") (pin "289") (pinfunction "289_289") (pintype "passive+no_connect"))
    )
    (net (code "149") (name "unconnected-(J6-Pad292)") (class "Default")
      (node (ref "J6") (pin "292") (pinfunction "292_292") (pintype "passive+no_connect"))
    )
    (net (code "150") (name "unconnected-(J6-Pad293)") (class "Default")
      (node (ref "J6") (pin "293") (pinfunction "293_293") (pintype "passive+no_connect"))
    )
    (net (code "151") (name "unconnected-(J6-Pad295)") (class "Default")
      (node (ref "J6") (pin "295") (pinfunction "295_295") (pintype "passive+no_connect"))
    )
    (net (code "152") (name "unconnected-(J6-Pad296)") (class "Default")
      (node (ref "J6") (pin "296") (pinfunction "296_296") (pintype "passive+no_connect"))
    )
    (net (code "153") (name "unconnected-(J6-Pad298)") (class "Default")
      (node (ref "J6") (pin "298") (pinfunction "298_298") (pintype "passive+no_connect"))
    )
    (net (code "154") (name "unconnected-(J6-Pad299)") (class "Default")
      (node (ref "J6") (pin "299") (pinfunction "299_299") (pintype "passive+no_connect"))
    )
    (net (code "155") (name "unconnected-(J6-Pad302)") (class "Default")
      (node (ref "J6") (pin "302") (pinfunction "302_302") (pintype "passive+no_connect"))
    )
    (net (code "156") (name "unconnected-(J6-Pad303)") (class "Default")
      (node (ref "J6") (pin "303") (pinfunction "303_303") (pintype "passive+no_connect"))
    )
    (net (code "157") (name "unconnected-(J6-Pad305)") (class "Default")
      (node (ref "J6") (pin "305") (pinfunction "305_305") (pintype "passive+no_connect"))
    )
    (net (code "158") (name "unconnected-(J6-Pad306)") (class "Default")
      (node (ref "J6") (pin "306") (pinfunction "306_306") (pintype "passive+no_connect"))
    )
    (net (code "159") (name "unconnected-(J6-Pad308)") (class "Default")
      (node (ref "J6") (pin "308") (pinfunction "308_308") (pintype "passive+no_connect"))
    )
    (net (code "160") (name "unconnected-(J6-Pad309)") (class "Default")
      (node (ref "J6") (pin "309") (pinfunction "309_309") (pintype "passive+no_connect"))
    )
    (net (code "161") (name "unconnected-(J6-Pad312)") (class "Default")
      (node (ref "J6") (pin "312") (pinfunction "312_312") (pintype "passive+no_connect"))
    )
    (net (code "162") (name "unconnected-(J6-Pad313)") (class "Default")
      (node (ref "J6") (pin "313") (pinfunction "313_313") (pintype "passive+no_connect"))
    )
    (net (code "163") (name "unconnected-(J6-Pad315)") (class "Default")
      (node (ref "J6") (pin "315") (pinfunction "315_315") (pintype "passive+no_connect"))
    )
    (net (code "164") (name "unconnected-(J6-Pad316)") (class "Default")
      (node (ref "J6") (pin "316") (pinfunction "316_316") (pintype "passive+no_connect"))
    )
    (net (code "165") (name "unconnected-(J6-Pad318)") (class "Default")
      (node (ref "J6") (pin "318") (pinfunction "318_318") (pintype "passive+no_connect"))
    )
    (net (code "166") (name "unconnected-(J6-Pad319)") (class "Default")
      (node (ref "J6") (pin "319") (pinfunction "319_319") (pintype "passive+no_connect"))
    )
    (net (code "167") (name "unconnected-(J6-Pad322)") (class "Default")
      (node (ref "J6") (pin "322") (pinfunction "322_322") (pintype "passive+no_connect"))
    )
    (net (code "168") (name "unconnected-(J6-Pad323)") (class "Default")
      (node (ref "J6") (pin "323") (pinfunction "323_323") (pintype "passive+no_connect"))
    )
    (net (code "169") (name "unconnected-(J6-Pad325)") (class "Default")
      (node (ref "J6") (pin "325") (pinfunction "325_325") (pintype "passive+no_connect"))
    )
    (net (code "170") (name "unconnected-(J6-Pad326)") (class "Default")
      (node (ref "J6") (pin "326") (pinfunction "326_326") (pintype "passive+no_connect"))
    )
    (net (code "171") (name "unconnected-(J6-Pad328)") (class "Default")
      (node (ref "J6") (pin "328") (pinfunction "328_328") (pintype "passive+no_connect"))
    )
    (net (code "172") (name "unconnected-(J6-Pad329)") (class "Default")
      (node (ref "J6") (pin "329") (pinfunction "329_329") (pintype "passive+no_connect"))
    )
    (net (code "173") (name "unconnected-(J6-Pad332)") (class "Default")
      (node (ref "J6") (pin "332") (pinfunction "332_332") (pintype "passive+no_connect"))
    )
    (net (code "174") (name "unconnected-(J6-Pad333)") (class "Default")
      (node (ref "J6") (pin "333") (pinfunction "333_333") (pintype "passive+no_connect"))
    )
    (net (code "175") (name "unconnected-(J6-Pad335)") (class "Default")
      (node (ref "J6") (pin "335") (pinfunction "335_335") (pintype "passive+no_connect"))
    )
    (net (code "176") (name "unconnected-(J6-Pad336)") (class "Default")
      (node (ref "J6") (pin "336") (pinfunction "336_336") (pintype "passive+no_connect"))
    )
    (net (code "177") (name "unconnected-(J6-Pad338)") (class "Default")
      (node (ref "J6") (pin "338") (pinfunction "338_338") (pintype "passive+no_connect"))
    )
    (net (code "178") (name "unconnected-(J6-Pad339)") (class "Default")
      (node (ref "J6") (pin "339") (pinfunction "339_339") (pintype "passive+no_connect"))
    )
    (net (code "179") (name "unconnected-(J6-Pad342)") (class "Default")
      (node (ref "J6") (pin "342") (pinfunction "342_342") (pintype "passive+no_connect"))
    )
    (net (code "180") (name "unconnected-(J6-Pad343)") (class "Default")
      (node (ref "J6") (pin "343") (pinfunction "343_343") (pintype "passive+no_connect"))
    )
    (net (code "181") (name "unconnected-(J6-Pad345)") (class "Default")
      (node (ref "J6") (pin "345") (pinfunction "345_345") (pintype "passive+no_connect"))
    )
    (net (code "182") (name "unconnected-(J6-Pad346)") (class "Default")
      (node (ref "J6") (pin "346") (pinfunction "346_346") (pintype "passive+no_connect"))
    )
    (net (code "183") (name "unconnected-(J6-Pad348)") (class "Default")
      (node (ref "J6") (pin "348") (pinfunction "348_348") (pintype "passive+no_connect"))
    )
    (net (code "184") (name "unconnected-(J6-Pad349)") (class "Default")
      (node (ref "J6") (pin "349") (pinfunction "349_349") (pintype "passive+no_connect"))
    )
    (net (code "185") (name "unconnected-(J6-Pad352)") (class "Default")
      (node (ref "J6") (pin "352") (pinfunction "352_352") (pintype "passive+no_connect"))
    )
    (net (code "186") (name "unconnected-(J6-Pad353)") (class "Default")
      (node (ref "J6") (pin "353") (pinfunction "353_353") (pintype "passive+no_connect"))
    )
    (net (code "187") (name "unconnected-(J6-Pad355)") (class "Default")
      (node (ref "J6") (pin "355") (pinfunction "355_355") (pintype "passive+no_connect"))
    )
    (net (code "188") (name "unconnected-(J6-Pad356)") (class "Default")
      (node (ref "J6") (pin "356") (pinfunction "356_356") (pintype "passive+no_connect"))
    )
    (net (code "189") (name "unconnected-(J6-Pad358)") (class "Default")
      (node (ref "J6") (pin "358") (pinfunction "358_358") (pintype "passive+no_connect"))
    )
    (net (code "190") (name "unconnected-(J6-Pad359)") (class "Default")
      (node (ref "J6") (pin "359") (pinfunction "359_359") (pintype "passive+no_connect"))
    )
    (net (code "191") (name "unconnected-(J6-Pad362)") (class "Default")
      (node (ref "J6") (pin "362") (pinfunction "362_362") (pintype "passive+no_connect"))
    )
    (net (code "192") (name "unconnected-(J6-Pad363)") (class "Default")
      (node (ref "J6") (pin "363") (pinfunction "363_363") (pintype "passive+no_connect"))
    )
    (net (code "193") (name "unconnected-(J6-Pad365)") (class "Default")
      (node (ref "J6") (pin "365") (pinfunction "365_365") (pintype "passive+no_connect"))
    )
    (net (code "194") (name "unconnected-(J6-Pad366)") (class "Default")
      (node (ref "J6") (pin "366") (pinfunction "366_366") (pintype "passive+no_connect"))
    )
    (net (code "195") (name "unconnected-(J6-Pad368)") (class "Default")
      (node (ref "J6") (pin "368") (pinfunction "368_368") (pintype "passive+no_connect"))
    )
    (net (code "196") (name "unconnected-(J6-Pad369)") (class "Default")
      (node (ref "J6") (pin "369") (pinfunction "369_369") (pintype "passive+no_connect"))
    )
    (net (code "197") (name "unconnected-(J6-Pad372)") (class "Default")
      (node (ref "J6") (pin "372") (pinfunction "372_372") (pintype "passive+no_connect"))
    )
    (net (code "198") (name "unconnected-(J6-Pad373)") (class "Default")
      (node (ref "J6") (pin "373") (pinfunction "373_373") (pintype "passive+no_connect"))
    )
    (net (code "199") (name "unconnected-(J6-Pad375)") (class "Default")
      (node (ref "J6") (pin "375") (pinfunction "375_375") (pintype "passive+no_connect"))
    )
    (net (code "200") (name "unconnected-(J6-Pad376)") (class "Default")
      (node (ref "J6") (pin "376") (pinfunction "376_376") (pintype "passive+no_connect"))
    )
    (net (code "201") (name "unconnected-(J6-Pad378)") (class "Default")
      (node (ref "J6") (pin "378") (pinfunction "378_378") (pintype "passive+no_connect"))
    )
    (net (code "202") (name "unconnected-(J6-Pad379)") (class "Default")
      (node (ref "J6") (pin "379") (pinfunction "379_379") (pintype "passive+no_connect"))
    )
    (net (code "203") (name "unconnected-(J6-Pad382)") (class "Default")
      (node (ref "J6") (pin "382") (pinfunction "382_382") (pintype "passive+no_connect"))
    )
    (net (code "204") (name "unconnected-(J6-Pad383)") (class "Default")
      (node (ref "J6") (pin "383") (pinfunction "383_383") (pintype "passive+no_connect"))
    )
    (net (code "205") (name "unconnected-(J6-Pad385)") (class "Default")
      (node (ref "J6") (pin "385") (pinfunction "385_385") (pintype "passive+no_connect"))
    )
    (net (code "206") (name "unconnected-(J6-Pad386)") (class "Default")
      (node (ref "J6") (pin "386") (pinfunction "386_386") (pintype "passive+no_connect"))
    )
    (net (code "207") (name "unconnected-(J6-Pad388)") (class "Default")
      (node (ref "J6") (pin "388") (pinfunction "388_388") (pintype "passive+no_connect"))
    )
    (net (code "208") (name "unconnected-(J6-Pad389)") (class "Default")
      (node (ref "J6") (pin "389") (pinfunction "389_389") (pintype "passive+no_connect"))
    )
    (net (code "209") (name "unconnected-(J6-Pad399)") (class "Default")
      (node (ref "J6") (pin "399") (pinfunction "399_399") (pintype "passive+no_connect"))
    )
    (net (code "210") (name "unconnected-(U68-A-Pad1)") (class "Default")
      (node (ref "U68") (pin "1") (pinfunction "A_1") (pintype "passive"))
    )
    (net (code "211") (name "unconnected-(U68-B-Pad3)") (class "Default")
      (node (ref "U68") (pin "3") (pinfunction "B_3") (pintype "passive"))
    )
    (net (code "212") (name "unconnected-(U68-C-Pad4)") (class "Default")
      (node (ref "U68") (pin "4") (pinfunction "C_4") (pintype "passive+no_connect"))
    )
    (net (code "213") (name "unconnected-(U70-A-Pad1)") (class "Default")
      (node (ref "U70") (pin "1") (pinfunction "A_1") (pintype "passive"))
    )
    (net (code "214") (name "unconnected-(U70-C-Pad4)") (class "Default")
      (node (ref "U70") (pin "4") (pinfunction "C_4") (pintype "passive+no_connect"))
    )
    (net (code "215") (name "unconnected-(U70-D-Pad6)") (class "Default")
      (node (ref "U70") (pin "6") (pinfunction "D_6") (pintype "passive"))
    )
  )
)
